# UselessBox.net
KiCad netlist of a schematic drawn in EAGLE
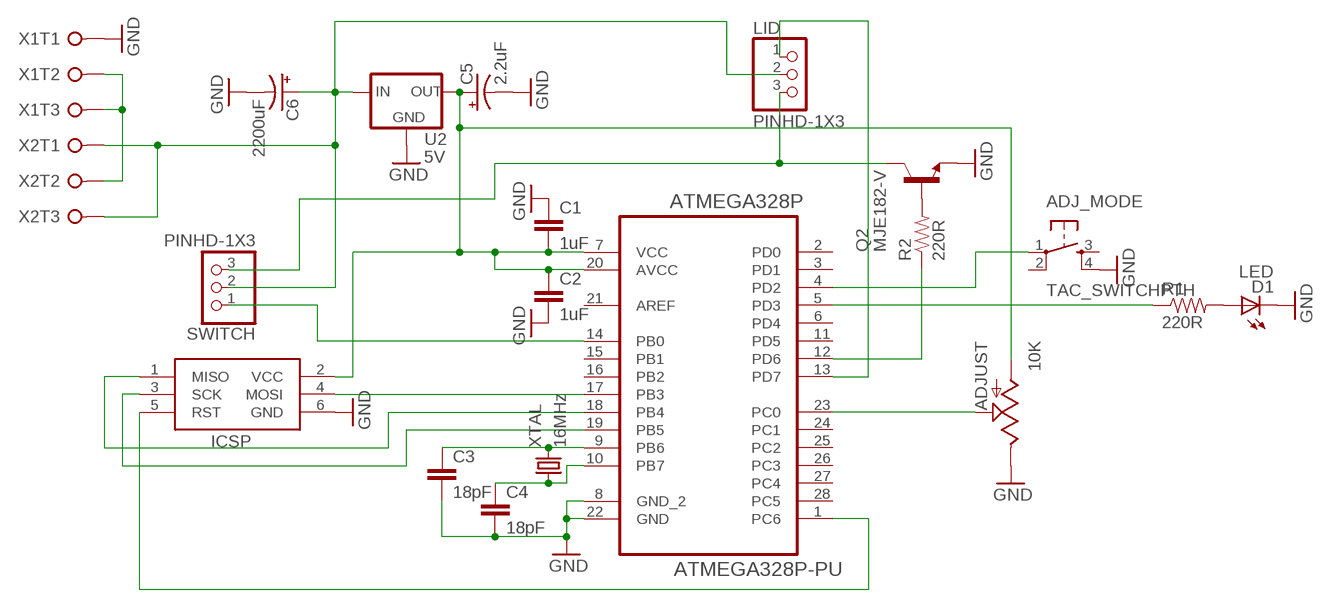
[diagram p0: schematic, sheet 1]

(export (version "E")
  (design (tool "Eeschema 10.0.6"))
  (components
    (comp (ref "ADJUST")
      (value "10K")
      (footprint "eagle-import:POT-3362U")
      (libsource (lib "eagle-import") (part "POT100K_3362U"))
    )
    (comp (ref "ADJ_MODE")
      (value "TAC_SWITCHPTH")
      (footprint "eagle-import:TACTILE-SWITCH-6MM")
      (libsource (lib "eagle-import") (part "TAC_SWITCHPTH"))
    )
    (comp (ref "ATMEGA328P")
      (value "ATMEGA328P-PU")
      (footprint "eagle-import:DIP28")
      (libsource (lib "eagle-import") (part "ATMEGA328P-PU"))
    )
    (comp (ref "C1")
      (value "1uF")
      (footprint "eagle-import:CAPACITOR-5MM")
      (libsource (lib "eagle-import") (part "CAPACITOR-5MM"))
    )
    (comp (ref "C2")
      (value "1uF")
      (footprint "eagle-import:CAPACITOR-5MM")
      (libsource (lib "eagle-import") (part "CAPACITOR-5MM"))
    )
    (comp (ref "C3")
      (value "18pF")
      (footprint "eagle-import:CAPACITOR-2.5MM")
      (libsource (lib "eagle-import") (part "CAPACITOR-2.5MM"))
    )
    (comp (ref "C4")
      (value "18pF")
      (footprint "eagle-import:CAPACITOR-2.5MM")
      (libsource (lib "eagle-import") (part "CAPACITOR-2.5MM"))
    )
    (comp (ref "C5")
      (value "2.2uF")
      (footprint "eagle-import:CAP-POL-2.5-5")
      (libsource (lib "eagle-import") (part "CAP-POL-2.5-5"))
    )
    (comp (ref "C6")
      (value "2200uF")
      (footprint "eagle-import:CAP-POL-5-10")
      (libsource (lib "eagle-import") (part "CAP-POL-5-10"))
    )
    (comp (ref "D1")
      (value "LED")
      (footprint "eagle-import:LED5MM")
      (libsource (lib "eagle-import") (part "LED"))
    )
    (comp (ref "ICSP")
      (value "AVRISP-6")
      (footprint "eagle-import:AVRISP")
      (libsource (lib "eagle-import") (part "AVRISP-6"))
    )
    (comp (ref "LID")
      (value "PINHD-1X3")
      (footprint "eagle-import:1X03")
      (libsource (lib "eagle-import") (part "PINHD-1X3"))
    )
    (comp (ref "Q2")
      (value "MJE182-V")
      (footprint "eagle-import:TO225AA-V")
      (libsource (lib "eagle-import") (part "MJE182-V"))
    )
    (comp (ref "R1")
      (value "220R")
      (footprint "eagle-import:AXIAL-7.5MM")
      (libsource (lib "eagle-import") (part "RESISTOR-7.5MM"))
    )
    (comp (ref "R2")
      (value "220R")
      (footprint "eagle-import:AXIAL-7.5MM")
      (libsource (lib "eagle-import") (part "RESISTOR-7.5MM"))
    )
    (comp (ref "SWITCH")
      (value "PINHD-1X3")
      (footprint "eagle-import:1X03")
      (libsource (lib "eagle-import") (part "PINHD-1X3"))
    )
    (comp (ref "U2")
      (value "5V")
      (footprint "eagle-import:TO92-INLINE")
      (libsource (lib "eagle-import") (part "LP2950"))
    )
    (comp (ref "X1")
      (value "SCREW-TERM-3")
      (footprint "eagle-import:SCREW-TERM-3")
      (libsource (lib "eagle-import") (part "SCREW-TERM-3"))
    )
    (comp (ref "X2")
      (value "SCREW-TERM-3")
      (footprint "eagle-import:SCREW-TERM-3")
      (libsource (lib "eagle-import") (part "SCREW-TERM-3"))
    )
    (comp (ref "XTAL")
      (value "16MHz")
      (footprint "eagle-import:CRYSTAL-V")
      (libsource (lib "eagle-import") (part "CRYSTAL-V"))
    )
  )
  (nets
    (net (code "1") (name "GND") (class "Default")
      (node (ref "ADJUST") (pin "P$1") (pinfunction "E_P$1") (pintype "passive"))
      (node (ref "ADJ_MODE") (pin "4") (pinfunction "4_4") (pintype "passive"))
      (node (ref "ATMEGA328P") (pin "22") (pinfunction "GND_22") (pintype "passive"))
      (node (ref "ATMEGA328P") (pin "8") (pinfunction "GND_2_8") (pintype "passive"))
      (node (ref "C1") (pin "1") (pinfunction "1_1") (pintype "passive"))
      (node (ref "C2") (pin "2") (pinfunction "2_2") (pintype "passive"))
      (node (ref "C3") (pin "2") (pinfunction "2_2") (pintype "passive"))
      (node (ref "C4") (pin "2") (pinfunction "2_2") (pintype "passive"))
      (node (ref "C5") (pin "-") (pinfunction "-_-") (pintype "passive"))
      (node (ref "C6") (pin "-") (pinfunction "-_-") (pintype "passive"))
      (node (ref "D1") (pin "K") (pinfunction "C_K") (pintype "passive"))
      (node (ref "ICSP") (pin "6") (pinfunction "GND_6") (pintype "power_in"))
      (node (ref "Q2") (pin "E") (pinfunction "E_E") (pintype "passive"))
      (node (ref "U2") (pin "2") (pinfunction "GND_2") (pintype "input"))
      (node (ref "X1") (pin "1") (pinfunction "KL_1") (pintype "passive"))
    )
    (net (code "2") (name "Net-(ADJUST-A)") (class "Default")
      (node (ref "ADJUST") (pin "P$3") (pinfunction "A_P$3") (pintype "passive"))
      (node (ref "ATMEGA328P") (pin "20") (pinfunction "AVCC_20") (pintype "power_in"))
      (node (ref "ATMEGA328P") (pin "7") (pinfunction "VCC_7") (pintype "power_in"))
      (node (ref "C1") (pin "2") (pinfunction "2_2") (pintype "passive"))
      (node (ref "C2") (pin "1") (pinfunction "1_1") (pintype "passive"))
      (node (ref "C5") (pin "+") (pinfunction "+_+") (pintype "passive"))
      (node (ref "ICSP") (pin "2") (pinfunction "VCC_2") (pintype "power_in"))
      (node (ref "U2") (pin "1") (pinfunction "OUT_1") (pintype "passive"))
    )
    (net (code "3") (name "Net-(ADJUST-S)") (class "Default")
      (node (ref "ADJUST") (pin "P$2") (pinfunction "S_P$2") (pintype "passive"))
      (node (ref "ATMEGA328P") (pin "23") (pinfunction "PC0_23") (pintype "bidirectional"))
    )
    (net (code "4") (name "Net-(ATMEGA328P-PB0)") (class "Default")
      (node (ref "ATMEGA328P") (pin "14") (pinfunction "PB0_14") (pintype "bidirectional"))
      (node (ref "SWITCH") (pin "1") (pinfunction "1_1") (pintype "passive"))
    )
    (net (code "5") (name "Net-(ATMEGA328P-PB3)") (class "Default")
      (node (ref "ATMEGA328P") (pin "17") (pinfunction "PB3_17") (pintype "bidirectional"))
      (node (ref "ICSP") (pin "4") (pinfunction "MOSI_4") (pintype "output"))
    )
    (net (code "6") (name "Net-(ATMEGA328P-PB4)") (class "Default")
      (node (ref "ATMEGA328P") (pin "18") (pinfunction "PB4_18") (pintype "bidirectional"))
      (node (ref "ICSP") (pin "1") (pinfunction "MISO_1") (pintype "input"))
    )
    (net (code "7") (name "Net-(ATMEGA328P-PB5)") (class "Default")
      (node (ref "ATMEGA328P") (pin "19") (pinfunction "PB5_19") (pintype "bidirectional"))
      (node (ref "ICSP") (pin "3") (pinfunction "SCK_3") (pintype "output"))
    )
    (net (code "8") (name "Net-(ATMEGA328P-PB6)") (class "Default")
      (node (ref "ATMEGA328P") (pin "9") (pinfunction "PB6_9") (pintype "bidirectional"))
      (node (ref "C3") (pin "1") (pinfunction "1_1") (pintype "passive"))
      (node (ref "XTAL") (pin "2") (pinfunction "2_2") (pintype "passive"))
    )
    (net (code "9") (name "Net-(ATMEGA328P-PB7)") (class "Default")
      (node (ref "ATMEGA328P") (pin "10") (pinfunction "PB7_10") (pintype "bidirectional"))
      (node (ref "C4") (pin "1") (pinfunction "1_1") (pintype "passive"))
      (node (ref "XTAL") (pin "1") (pinfunction "1_1") (pintype "passive"))
    )
    (net (code "10") (name "Net-(ATMEGA328P-PC6)") (class "Default")
      (node (ref "ATMEGA328P") (pin "1") (pinfunction "PC6_1") (pintype "bidirectional"))
      (node (ref "ICSP") (pin "5") (pinfunction "RST_5") (pintype "output"))
    )
    (net (code "11") (name "Net-(ATMEGA328P-PD2)") (class "Default")
      (node (ref "ADJ_MODE") (pin "1") (pinfunction "1_1") (pintype "passive"))
      (node (ref "ATMEGA328P") (pin "4") (pinfunction "PD2_4") (pintype "bidirectional"))
    )
    (net (code "12") (name "Net-(ATMEGA328P-PD3)") (class "Default")
      (node (ref "ATMEGA328P") (pin "5") (pinfunction "PD3_5") (pintype "bidirectional"))
      (node (ref "R1") (pin "P$1") (pinfunction "1_P$1") (pintype "passive"))
    )
    (net (code "13") (name "Net-(ATMEGA328P-PD6)") (class "Default")
      (node (ref "ATMEGA328P") (pin "12") (pinfunction "PD6_12") (pintype "bidirectional"))
      (node (ref "R2") (pin "P$1") (pinfunction "1_P$1") (pintype "passive"))
    )
    (net (code "14") (name "Net-(ATMEGA328P-PD7)") (class "Default")
      (node (ref "ATMEGA328P") (pin "13") (pinfunction "PD7_13") (pintype "bidirectional"))
      (node (ref "LID") (pin "1") (pinfunction "1_1") (pintype "passive"))
    )
    (net (code "15") (name "Net-(LID-Pad3)") (class "Default")
      (node (ref "LID") (pin "3") (pinfunction "3_3") (pintype "passive"))
      (node (ref "Q2") (pin "C") (pinfunction "C_C") (pintype "passive"))
      (node (ref "SWITCH") (pin "3") (pinfunction "3_3") (pintype "passive"))
    )
    (net (code "16") (name "Net-(R1-2)") (class "Default")
      (node (ref "D1") (pin "A") (pinfunction "A_A") (pintype "passive"))
      (node (ref "R1") (pin "P$2") (pinfunction "2_P$2") (pintype "passive"))
    )
    (net (code "17") (name "Net-(R2-2)") (class "Default")
      (node (ref "Q2") (pin "B") (pinfunction "B_B") (pintype "passive"))
      (node (ref "R2") (pin "P$2") (pinfunction "2_P$2") (pintype "passive"))
    )
    (net (code "18") (name "Net-(U2-IN)") (class "Default")
      (node (ref "C6") (pin "+") (pinfunction "+_+") (pintype "passive"))
      (node (ref "LID") (pin "2") (pinfunction "2_2") (pintype "passive"))
      (node (ref "SWITCH") (pin "2") (pinfunction "2_2") (pintype "passive"))
      (node (ref "U2") (pin "3") (pinfunction "IN_3") (pintype "input"))
      (node (ref "X2") (pin "1") (pinfunction "KL_1") (pintype "passive"))
      (node (ref "X2") (pin "3") (pinfunction "KL_3") (pintype "passive"))
    )
    (net (code "19") (name "Net-(X1B-KL)") (class "Default")
      (node (ref "X1") (pin "2") (pinfunction "KL_2") (pintype "passive"))
      (node (ref "X1") (pin "3") (pinfunction "KL_3") (pintype "passive"))
      (node (ref "X2") (pin "2") (pinfunction "KL_2") (pintype "passive"))
    )
    (net (code "20") (name "unconnected-(ADJ_MODE-Pad2)") (class "Default")
      (node (ref "ADJ_MODE") (pin "2") (pinfunction "2_2") (pintype "passive"))
    )
    (net (code "21") (name "unconnected-(ADJ_MODE-Pad3)") (class "Default")
      (node (ref "ADJ_MODE") (pin "3") (pinfunction "3_3") (pintype "passive"))
    )
    (net (code "22") (name "unconnected-(ATMEGA328P-AREF-Pad21)") (class "Default")
      (node (ref "ATMEGA328P") (pin "21") (pinfunction "AREF_21") (pintype "input"))
    )
    (net (code "23") (name "unconnected-(ATMEGA328P-PB1-Pad15)") (class "Default")
      (node (ref "ATMEGA328P") (pin "15") (pinfunction "PB1_15") (pintype "bidirectional"))
    )
    (net (code "24") (name "unconnected-(ATMEGA328P-PB2-Pad16)") (class "Default")
      (node (ref "ATMEGA328P") (pin "16") (pinfunction "PB2_16") (pintype "bidirectional"))
    )
    (net (code "25") (name "unconnected-(ATMEGA328P-PC1-Pad24)") (class "Default")
      (node (ref "ATMEGA328P") (pin "24") (pinfunction "PC1_24") (pintype "bidirectional"))
    )
    (net (code "26") (name "unconnected-(ATMEGA328P-PC2-Pad25)") (class "Default")
      (node (ref "ATMEGA328P") (pin "25") (pinfunction "PC2_25") (pintype "bidirectional"))
    )
    (net (code "27") (name "unconnected-(ATMEGA328P-PC3-Pad26)") (class "Default")
      (node (ref "ATMEGA328P") (pin "26") (pinfunction "PC3_26") (pintype "bidirectional"))
    )
    (net (code "28") (name "unconnected-(ATMEGA328P-PC4-Pad27)") (class "Default")
      (node (ref "ATMEGA328P") (pin "27") (pinfunction "PC4_27") (pintype "bidirectional"))
    )
    (net (code "29") (name "unconnected-(ATMEGA328P-PC5-Pad28)") (class "Default")
      (node (ref "ATMEGA328P") (pin "28") (pinfunction "PC5_28") (pintype "bidirectional"))
    )
    (net (code "30") (name "unconnected-(ATMEGA328P-PD0-Pad2)") (class "Default")
      (node (ref "ATMEGA328P") (pin "2") (pinfunction "PD0_2") (pintype "bidirectional"))
    )
    (net (code "31") (name "unconnected-(ATMEGA328P-PD1-Pad3)") (class "Default")
      (node (ref "ATMEGA328P") (pin "3") (pinfunction "PD1_3") (pintype "bidirectional"))
    )
    (net (code "32") (name "unconnected-(ATMEGA328P-PD4-Pad6)") (class "Default")
      (node (ref "ATMEGA328P") (pin "6") (pinfunction "PD4_6") (pintype "bidirectional"))
    )
    (net (code "33") (name "unconnected-(ATMEGA328P-PD5-Pad11)") (class "Default")
      (node (ref "ATMEGA328P") (pin "11") (pinfunction "PD5_11") (pintype "bidirectional"))
    )
  )
)
